# Storage_Memory.net
KiCad netlist of a schematic drawn in Altium Designer
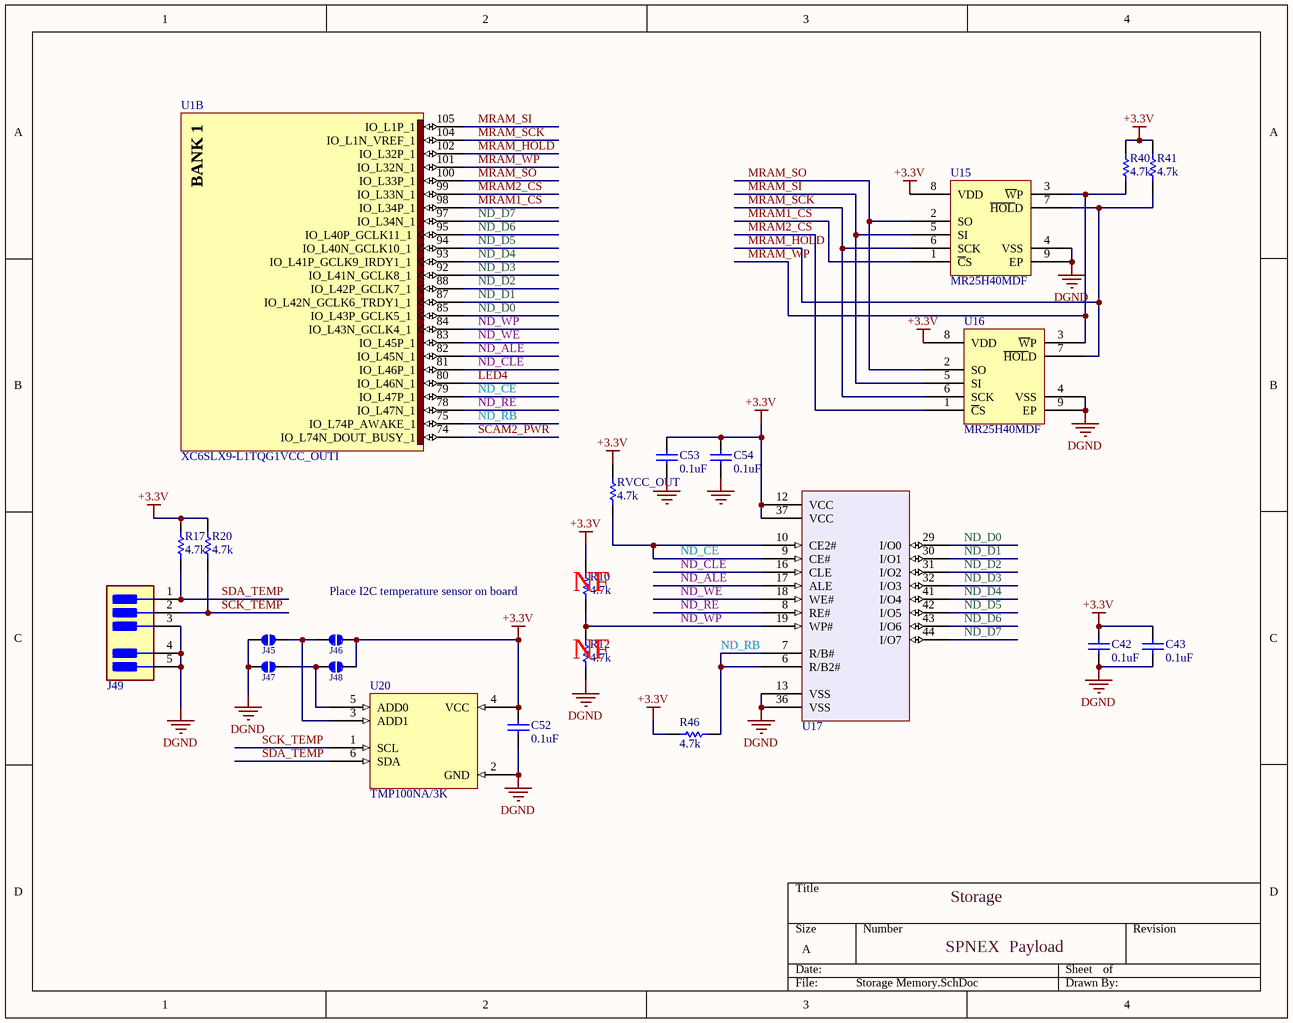
[diagram p0: Storage Memory.SchDoc]

(export (version "E")
  (design (tool "Eeschema 10.0.6"))
  (components
    (comp (ref "C42")
      (value "0.1uF")
      (footprint "0805CAP")
      (description "Surface Mount Ceramic Multilayer Capacitor 0.1uF 10% X7R 16V 0805 Paper T/R")
      (fields
        (field (name "MANUFACTURER") "Yageo")
        (field (name "MANUFACTURER PART NUMBER") "CC0805KRX7R7BB104")
      )
      (libsource (lib "Spnex_lib") (part "CAP_CER_0.1uf_10V_0805"))
    )
    (comp (ref "C43")
      (value "0.1uF")
      (footprint "0805CAP")
      (description "Surface Mount Ceramic Multilayer Capacitor 0.1uF 10% X7R 16V 0805 Paper T/R")
      (fields
        (field (name "MANUFACTURER") "Yageo")
        (field (name "MANUFACTURER PART NUMBER") "CC0805KRX7R7BB104")
      )
      (libsource (lib "Spnex_lib") (part "CAP_CER_0.1uf_10V_0805"))
    )
    (comp (ref "C52")
      (value "0.1uF")
      (footprint "0805CAP")
      (description "Surface Mount Ceramic Multilayer Capacitor 0.1uF 10% X7R 16V 0805 Paper T/R")
      (fields
        (field (name "MANUFACTURER") "Yageo")
        (field (name "MANUFACTURER PART NUMBER") "CC0805KRX7R7BB104")
      )
      (libsource (lib "Spnex_library") (part "CAP_CER_0.1uf_10V_0805"))
    )
    (comp (ref "C53")
      (value "0.1uF")
      (footprint "0805 - CAP")
      (description "CAP CER 0.1UF 16V X7R 0805")
      (fields
        (field (name "MANUFACTURER") "Samsung Electro-Mechanics America, Inc.")
        (field (name "MANUFACTURER PART NUMBER") "CL21B104KOANNNC")
      )
      (libsource (lib "Kh_Lib") (part "Cap_CER_0.1U_16V_0805"))
    )
    (comp (ref "C54")
      (value "0.1uF")
      (footprint "0805 - CAP")
      (description "CAP CER 0.1UF 16V X7R 0805")
      (fields
        (field (name "MANUFACTURER") "Samsung Electro-Mechanics America, Inc.")
        (field (name "MANUFACTURER PART NUMBER") "CL21B104KOANNNC")
      )
      (libsource (lib "Kh_Lib") (part "Cap_CER_0.1U_16V_0805"))
    )
    (comp (ref "J45")
      (value "JUMPER")
      (footprint "SJMP")
      (description "OPTION SELECTION PAD")
      (libsource (lib "Kh_Lib") (part "JUMPER"))
    )
    (comp (ref "J46")
      (value "JUMPER")
      (footprint "SJMP")
      (description "OPTION SELECTION PAD")
      (libsource (lib "Kh_Lib") (part "JUMPER"))
    )
    (comp (ref "J47")
      (value "JUMPER")
      (footprint "SJMP")
      (description "OPTION SELECTION PAD")
      (libsource (lib "Kh_Lib") (part "JUMPER"))
    )
    (comp (ref "J48")
      (value "JUMPER")
      (footprint "SJMP")
      (description "OPTION SELECTION PAD")
      (libsource (lib "Kh_Lib") (part "JUMPER"))
    )
    (comp (ref "J49")
      (value "53261-0371")
      (footprint "FP-53261-0371-MFG")
      (description "Conn Shrouded Header HDR 3 POS 1.25mm Solder RA SMD PicoBlade™ Embossed T/R")
      (fields (field (name "MANUFACTURER") "Molex"))
      (libsource (lib "Spnex_library") (part "0532610371"))
    )
    (comp (ref "R10")
      (value "RES_4.7K_0.1W_0603")
      (footprint "0603RES")
      (description "Resistor")
      (fields
        (field (name "MANUFACTURER") "Stackpole Electronics Inc.")
        (field (name "MANUFACTURER PART NUMBER") "RMCF0603JT4K70")
        (field (name "RESISTANCE (OHMS)") "4.7k")
      )
      (libsource (lib "Spnex_lib") (part "RES_4.7K_0.1W_0603"))
    )
    (comp (ref "R12")
      (value "RES_4.7K_0.1W_0603")
      (footprint "0603RES")
      (description "Resistor")
      (fields
        (field (name "MANUFACTURER") "Stackpole Electronics Inc.")
        (field (name "MANUFACTURER PART NUMBER") "RMCF0603JT4K70")
        (field (name "RESISTANCE (OHMS)") "4.7k")
      )
      (libsource (lib "Spnex_lib") (part "RES_4.7K_0.1W_0603"))
    )
    (comp (ref "R17")
      (value "RES_4.7K_0.1W_0603")
      (footprint "0603RES")
      (description "Resistor")
      (fields
        (field (name "MANUFACTURER") "Stackpole Electronics Inc.")
        (field (name "MANUFACTURER PART NUMBER") "RMCF0603JT4K70")
        (field (name "RESISTANCE (OHMS)") "4.7k")
      )
      (libsource (lib "Spnex_library") (part "RES_4.7K_0.1W_0603"))
    )
    (comp (ref "R20")
      (value "RES_4.7K_0.1W_0603")
      (footprint "0603RES")
      (description "Resistor")
      (fields
        (field (name "MANUFACTURER") "Stackpole Electronics Inc.")
        (field (name "MANUFACTURER PART NUMBER") "RMCF0603JT4K70")
        (field (name "RESISTANCE (OHMS)") "4.7k")
      )
      (libsource (lib "Spnex_library") (part "RES_4.7K_0.1W_0603"))
    )
    (comp (ref "R40")
      (value "RES_4.7K_0.1W_0603")
      (footprint "0603RES")
      (description "Resistor")
      (fields
        (field (name "MANUFACTURER") "Stackpole Electronics Inc.")
        (field (name "MANUFACTURER PART NUMBER") "RMCF0603JT4K70")
        (field (name "RESISTANCE (OHMS)") "4.7k")
      )
      (libsource (lib "Spnex_lib") (part "RES_4.7K_0.1W_0603"))
    )
    (comp (ref "R41")
      (value "RES_4.7K_0.1W_0603")
      (footprint "0603RES")
      (description "Resistor")
      (fields
        (field (name "MANUFACTURER") "Stackpole Electronics Inc.")
        (field (name "MANUFACTURER PART NUMBER") "RMCF0603JT4K70")
        (field (name "RESISTANCE (OHMS)") "4.7k")
      )
      (libsource (lib "Spnex_lib") (part "RES_4.7K_0.1W_0603"))
    )
    (comp (ref "R46")
      (value "RES_4.7K_0.1W_0603")
      (footprint "0603RES")
      (description "Resistor")
      (fields
        (field (name "MANUFACTURER") "Stackpole Electronics Inc.")
        (field (name "MANUFACTURER PART NUMBER") "RMCF0603JT4K70")
        (field (name "RESISTANCE (OHMS)") "4.7k")
      )
      (libsource (lib "Spnex_lib") (part "RES_4.7K_0.1W_0603"))
    )
    (comp (ref "RVCC_OUT")
      (value "RES_4.7K_0.1W_0603")
      (footprint "0603RES")
      (description "Resistor")
      (fields
        (field (name "MANUFACTURER") "Stackpole Electronics Inc.")
        (field (name "MANUFACTURER PART NUMBER") "RMCF0603JT4K70")
        (field (name "RESISTANCE (OHMS)") "4.7k")
      )
      (libsource (lib "Spnex_lib") (part "RES_4.7K_0.1W_0603"))
    )
    (comp (ref "U1")
      (value "XC6SLX9-L1TQG1VCC_OUTI")
      (footprint "TQG144_M")
      (fields (field (name "PUBLISHER") "Altium Limited"))
      (libsource (lib "Spnex_lib") (part "XC6SLX9-L1TQG144I"))
    )
    (comp (ref "U15")
      (value "MR25H40MDF")
      (footprint "DFN8")
      (description "IC MRAM 4MBIT 40MHZ 8DFN")
      (fields (field (name "MANUFACTURER") "Everspin Technologies Inc."))
      (libsource (lib "Spnex_lib") (part "MR25H40MDF"))
    )
    (comp (ref "U16")
      (value "MR25H40MDF")
      (footprint "DFN8")
      (description "IC MRAM 4MBIT 40MHZ 8DFN")
      (fields (field (name "MANUFACTURER") "Everspin Technologies Inc."))
      (libsource (lib "Spnex_lib") (part "MR25H40MDF"))
    )
    (comp (ref "U17")
      (value "MT29F8G08AB")
      (footprint "VOG48")
      (description "8Gb x8 NAND Flash Memory")
      (fields
        (field (name "MANUFACTURER") "Micron Technology Inc")
        (field (name "DESIGNEDBY") "Circuitry Parts")
      )
      (libsource (lib "Spnex_lib") (part "MT29F32G08AFABAWP"))
    )
    (comp (ref "U20")
      (value "TMP100NA/3K")
      (footprint "SOT-23-6")
      (description "SENSOR TEMP I2C/SMBUS SOT23-6")
      (fields
        (field (name "MANUFACTURER") "Texas Instruments")
        (field (name "MANUFACTURER PART NUMBER") "TMP100NA/3K")
      )
      (libsource (lib "Spnex_library") (part "Temp_Sensor_I2C"))
    )
  )
  (nets
    (net (code "1") (name "+3.3V") (class "Default")
      (node (ref "C42") (pin "2") (pinfunction "2_2") (pintype "passive"))
      (node (ref "C43") (pin "2") (pinfunction "2_2") (pintype "passive"))
      (node (ref "C52") (pin "2") (pinfunction "2_2") (pintype "passive"))
      (node (ref "C53") (pin "2") (pinfunction "2_2") (pintype "passive"))
      (node (ref "C54") (pin "2") (pinfunction "2_2") (pintype "passive"))
      (node (ref "J46") (pin "1") (pinfunction "1_1") (pintype "passive"))
      (node (ref "J48") (pin "1") (pinfunction "1_1") (pintype "passive"))
      (node (ref "R10") (pin "2") (pinfunction "2_2") (pintype "passive"))
      (node (ref "R17") (pin "2") (pinfunction "2_2") (pintype "passive"))
      (node (ref "R20") (pin "2") (pinfunction "2_2") (pintype "passive"))
      (node (ref "R40") (pin "1") (pinfunction "1_1") (pintype "passive"))
      (node (ref "R41") (pin "1") (pinfunction "1_1") (pintype "passive"))
      (node (ref "R46") (pin "1") (pinfunction "1_1") (pintype "passive"))
      (node (ref "RVCC_OUT") (pin "2") (pinfunction "2_2") (pintype "passive"))
      (node (ref "U15") (pin "8") (pinfunction "VDD_8") (pintype "passive"))
      (node (ref "U16") (pin "8") (pinfunction "VDD_8") (pintype "passive"))
      (node (ref "U17") (pin "12") (pinfunction "VCC_12") (pintype "power_in"))
      (node (ref "U17") (pin "37") (pinfunction "VCC_37") (pintype "power_in"))
      (node (ref "U20") (pin "4") (pinfunction "VCC_4") (pintype "input"))
    )
    (net (code "2") (name "/LED4") (class "Default")
      (node (ref "U1") (pin "80") (pinfunction "IO_L46N_1_80") (pintype "bidirectional"))
    )
    (net (code "3") (name "/MRAM1_CS") (class "Default")
      (node (ref "U1") (pin "98") (pinfunction "IO_L34P_1_98") (pintype "bidirectional"))
      (node (ref "U15") (pin "1") (pinfunction "~{C}S_1") (pintype "passive"))
    )
    (net (code "4") (name "/MRAM2_CS") (class "Default")
      (node (ref "U1") (pin "99") (pinfunction "IO_L33N_1_99") (pintype "bidirectional"))
      (node (ref "U16") (pin "1") (pinfunction "~{C}S_1") (pintype "passive"))
    )
    (net (code "5") (name "/MRAM_HOLD") (class "Default")
      (node (ref "R41") (pin "2") (pinfunction "2_2") (pintype "passive"))
      (node (ref "U1") (pin "102") (pinfunction "IO_L32P_1_102") (pintype "bidirectional"))
      (node (ref "U15") (pin "7") (pinfunction "~{HOL}D_7") (pintype "passive"))
      (node (ref "U16") (pin "7") (pinfunction "~{HOL}D_7") (pintype "passive"))
    )
    (net (code "6") (name "/MRAM_SCK") (class "Default")
      (node (ref "U1") (pin "104") (pinfunction "IO_L1N_VREF_1_104") (pintype "bidirectional"))
      (node (ref "U15") (pin "6") (pinfunction "SCK_6") (pintype "passive"))
      (node (ref "U16") (pin "6") (pinfunction "SCK_6") (pintype "passive"))
    )
    (net (code "7") (name "/MRAM_SI") (class "Default")
      (node (ref "U1") (pin "105") (pinfunction "IO_L1P_1_105") (pintype "bidirectional"))
      (node (ref "U15") (pin "5") (pinfunction "SI_5") (pintype "passive"))
      (node (ref "U16") (pin "5") (pinfunction "SI_5") (pintype "passive"))
    )
    (net (code "8") (name "/MRAM_SO") (class "Default")
      (node (ref "U1") (pin "100") (pinfunction "IO_L33P_1_100") (pintype "bidirectional"))
      (node (ref "U15") (pin "2") (pinfunction "SO_2") (pintype "passive"))
      (node (ref "U16") (pin "2") (pinfunction "SO_2") (pintype "passive"))
    )
    (net (code "9") (name "/MRAM_WP") (class "Default")
      (node (ref "R40") (pin "2") (pinfunction "2_2") (pintype "passive"))
      (node (ref "U1") (pin "101") (pinfunction "IO_L32N_1_101") (pintype "bidirectional"))
      (node (ref "U15") (pin "3") (pinfunction "~{W}P_3") (pintype "passive"))
      (node (ref "U16") (pin "3") (pinfunction "~{W}P_3") (pintype "passive"))
    )
    (net (code "10") (name "/ND_ALE") (class "Default")
      (node (ref "U1") (pin "82") (pinfunction "IO_L45N_1_82") (pintype "bidirectional"))
      (node (ref "U17") (pin "17") (pinfunction "ALE_17") (pintype "input"))
    )
    (net (code "11") (name "/ND_CE") (class "Default")
      (node (ref "RVCC_OUT") (pin "1") (pinfunction "1_1") (pintype "passive"))
      (node (ref "U1") (pin "79") (pinfunction "IO_L47P_1_79") (pintype "bidirectional"))
      (node (ref "U17") (pin "10") (pinfunction "CE2#_10") (pintype "input"))
      (node (ref "U17") (pin "9") (pinfunction "CE#_9") (pintype "input"))
    )
    (net (code "12") (name "/ND_CLE") (class "Default")
      (node (ref "U1") (pin "81") (pinfunction "IO_L46P_1_81") (pintype "bidirectional"))
      (node (ref "U17") (pin "16") (pinfunction "CLE_16") (pintype "input"))
    )
    (net (code "13") (name "/ND_D0") (class "Default")
      (node (ref "U1") (pin "85") (pinfunction "IO_L43P_GCLK5_1_85") (pintype "bidirectional"))
      (node (ref "U17") (pin "29") (pinfunction "I/O0_29") (pintype "bidirectional"))
    )
    (net (code "14") (name "/ND_D1") (class "Default")
      (node (ref "U1") (pin "87") (pinfunction "IO_L42N_GCLK6_TRDY1_1_87") (pintype "bidirectional"))
      (node (ref "U17") (pin "30") (pinfunction "I/O1_30") (pintype "bidirectional"))
    )
    (net (code "15") (name "/ND_D2") (class "Default")
      (node (ref "U1") (pin "88") (pinfunction "IO_L42P_GCLK7_1_88") (pintype "bidirectional"))
      (node (ref "U17") (pin "31") (pinfunction "I/O2_31") (pintype "bidirectional"))
    )
    (net (code "16") (name "/ND_D3") (class "Default")
      (node (ref "U1") (pin "92") (pinfunction "IO_L41N_GCLK8_1_92") (pintype "bidirectional"))
      (node (ref "U17") (pin "32") (pinfunction "I/O3_32") (pintype "bidirectional"))
    )
    (net (code "17") (name "/ND_D4") (class "Default")
      (node (ref "U1") (pin "93") (pinfunction "IO_L41P_GCLK9_IRDY1_1_93") (pintype "bidirectional"))
      (node (ref "U17") (pin "41") (pinfunction "I/O4_41") (pintype "bidirectional"))
    )
    (net (code "18") (name "/ND_D5") (class "Default")
      (node (ref "U1") (pin "94") (pinfunction "IO_L40N_GCLK10_1_94") (pintype "bidirectional"))
      (node (ref "U17") (pin "42") (pinfunction "I/O5_42") (pintype "bidirectional"))
    )
    (net (code "19") (name "/ND_D6") (class "Default")
      (node (ref "U1") (pin "95") (pinfunction "IO_L40P_GCLK11_1_95") (pintype "bidirectional"))
      (node (ref "U17") (pin "43") (pinfunction "I/O6_43") (pintype "bidirectional"))
    )
    (net (code "20") (name "/ND_D7") (class "Default")
      (node (ref "U1") (pin "97") (pinfunction "IO_L34N_1_97") (pintype "bidirectional"))
      (node (ref "U17") (pin "44") (pinfunction "I/O7_44") (pintype "bidirectional"))
    )
    (net (code "21") (name "/ND_RB") (class "Default")
      (node (ref "R46") (pin "2") (pinfunction "2_2") (pintype "passive"))
      (node (ref "U1") (pin "75") (pinfunction "IO_L74P_AWAKE_1_75") (pintype "bidirectional"))
      (node (ref "U17") (pin "6") (pinfunction "R/B2#_6") (pintype "open_collector"))
      (node (ref "U17") (pin "7") (pinfunction "R/B#_7") (pintype "open_collector"))
    )
    (net (code "22") (name "/ND_RE") (class "Default")
      (node (ref "U1") (pin "78") (pinfunction "IO_L47N_1_78") (pintype "bidirectional"))
      (node (ref "U17") (pin "8") (pinfunction "RE#_8") (pintype "input"))
    )
    (net (code "23") (name "/ND_WE") (class "Default")
      (node (ref "U1") (pin "83") (pinfunction "IO_L45P_1_83") (pintype "bidirectional"))
      (node (ref "U17") (pin "18") (pinfunction "WE#_18") (pintype "input"))
    )
    (net (code "24") (name "/ND_WP") (class "Default")
      (node (ref "R10") (pin "1") (pinfunction "1_1") (pintype "passive"))
      (node (ref "R12") (pin "2") (pinfunction "2_2") (pintype "passive"))
      (node (ref "U1") (pin "84") (pinfunction "IO_L43N_GCLK4_1_84") (pintype "bidirectional"))
      (node (ref "U17") (pin "19") (pinfunction "WP#_19") (pintype "input"))
    )
    (net (code "25") (name "/SCAM2_PWR") (class "Default")
      (node (ref "U1") (pin "74") (pinfunction "IO_L74N_DOUT_BUSY_1_74") (pintype "bidirectional"))
    )
    (net (code "26") (name "/SCK_TEMP") (class "Default")
      (node (ref "J49") (pin "2") (pinfunction "2_2") (pintype "passive"))
      (node (ref "R20") (pin "1") (pinfunction "1_1") (pintype "passive"))
      (node (ref "U20") (pin "1") (pinfunction "SCL_1") (pintype "input"))
    )
    (net (code "27") (name "/SDA_TEMP") (class "Default")
      (node (ref "J49") (pin "1") (pinfunction "1_1") (pintype "passive"))
      (node (ref "R17") (pin "1") (pinfunction "1_1") (pintype "passive"))
      (node (ref "U20") (pin "6") (pinfunction "SDA_6") (pintype "input"))
    )
    (net (code "28") (name "DGND") (class "Default")
      (node (ref "C42") (pin "1") (pinfunction "1_1") (pintype "passive"))
      (node (ref "C43") (pin "1") (pinfunction "1_1") (pintype "passive"))
      (node (ref "C52") (pin "1") (pinfunction "1_1") (pintype "passive"))
      (node (ref "C53") (pin "1") (pinfunction "1_1") (pintype "passive"))
      (node (ref "C54") (pin "1") (pinfunction "1_1") (pintype "passive"))
      (node (ref "J45") (pin "2") (pinfunction "2_2") (pintype "passive"))
      (node (ref "J47") (pin "2") (pinfunction "2_2") (pintype "passive"))
      (node (ref "J49") (pin "3") (pinfunction "3_3") (pintype "passive"))
      (node (ref "J49") (pin "4") (pinfunction "4_4") (pintype "passive"))
      (node (ref "J49") (pin "5") (pinfunction "5_5") (pintype "passive"))
      (node (ref "R12") (pin "1") (pinfunction "1_1") (pintype "passive"))
      (node (ref "U15") (pin "4") (pinfunction "VSS_4") (pintype "passive"))
      (node (ref "U15") (pin "9") (pinfunction "EP_9") (pintype "passive"))
      (node (ref "U16") (pin "4") (pinfunction "VSS_4") (pintype "passive"))
      (node (ref "U16") (pin "9") (pinfunction "EP_9") (pintype "passive"))
      (node (ref "U17") (pin "13") (pinfunction "VSS_13") (pintype "power_in"))
      (node (ref "U17") (pin "36") (pinfunction "VSS_36") (pintype "power_in"))
      (node (ref "U20") (pin "2") (pinfunction "GND_2") (pintype "input"))
    )
    (net (code "29") (name "Net-(U20-ADD0)") (class "Default")
      (node (ref "J47") (pin "1") (pinfunction "1_1") (pintype "passive"))
      (node (ref "J48") (pin "2") (pinfunction "2_2") (pintype "passive"))
      (node (ref "U20") (pin "5") (pinfunction "ADD0_5") (pintype "input"))
    )
    (net (code "30") (name "Net-(U20-ADD1)") (class "Default")
      (node (ref "J45") (pin "1") (pinfunction "1_1") (pintype "passive"))
      (node (ref "J46") (pin "2") (pinfunction "2_2") (pintype "passive"))
      (node (ref "U20") (pin "3") (pinfunction "ADD1_3") (pintype "input"))
    )
  )
)
